# Adafruit_FXOS8700_FXAS21002_9_DoF_Breako.net
KiCad netlist of a schematic drawn in EAGLE
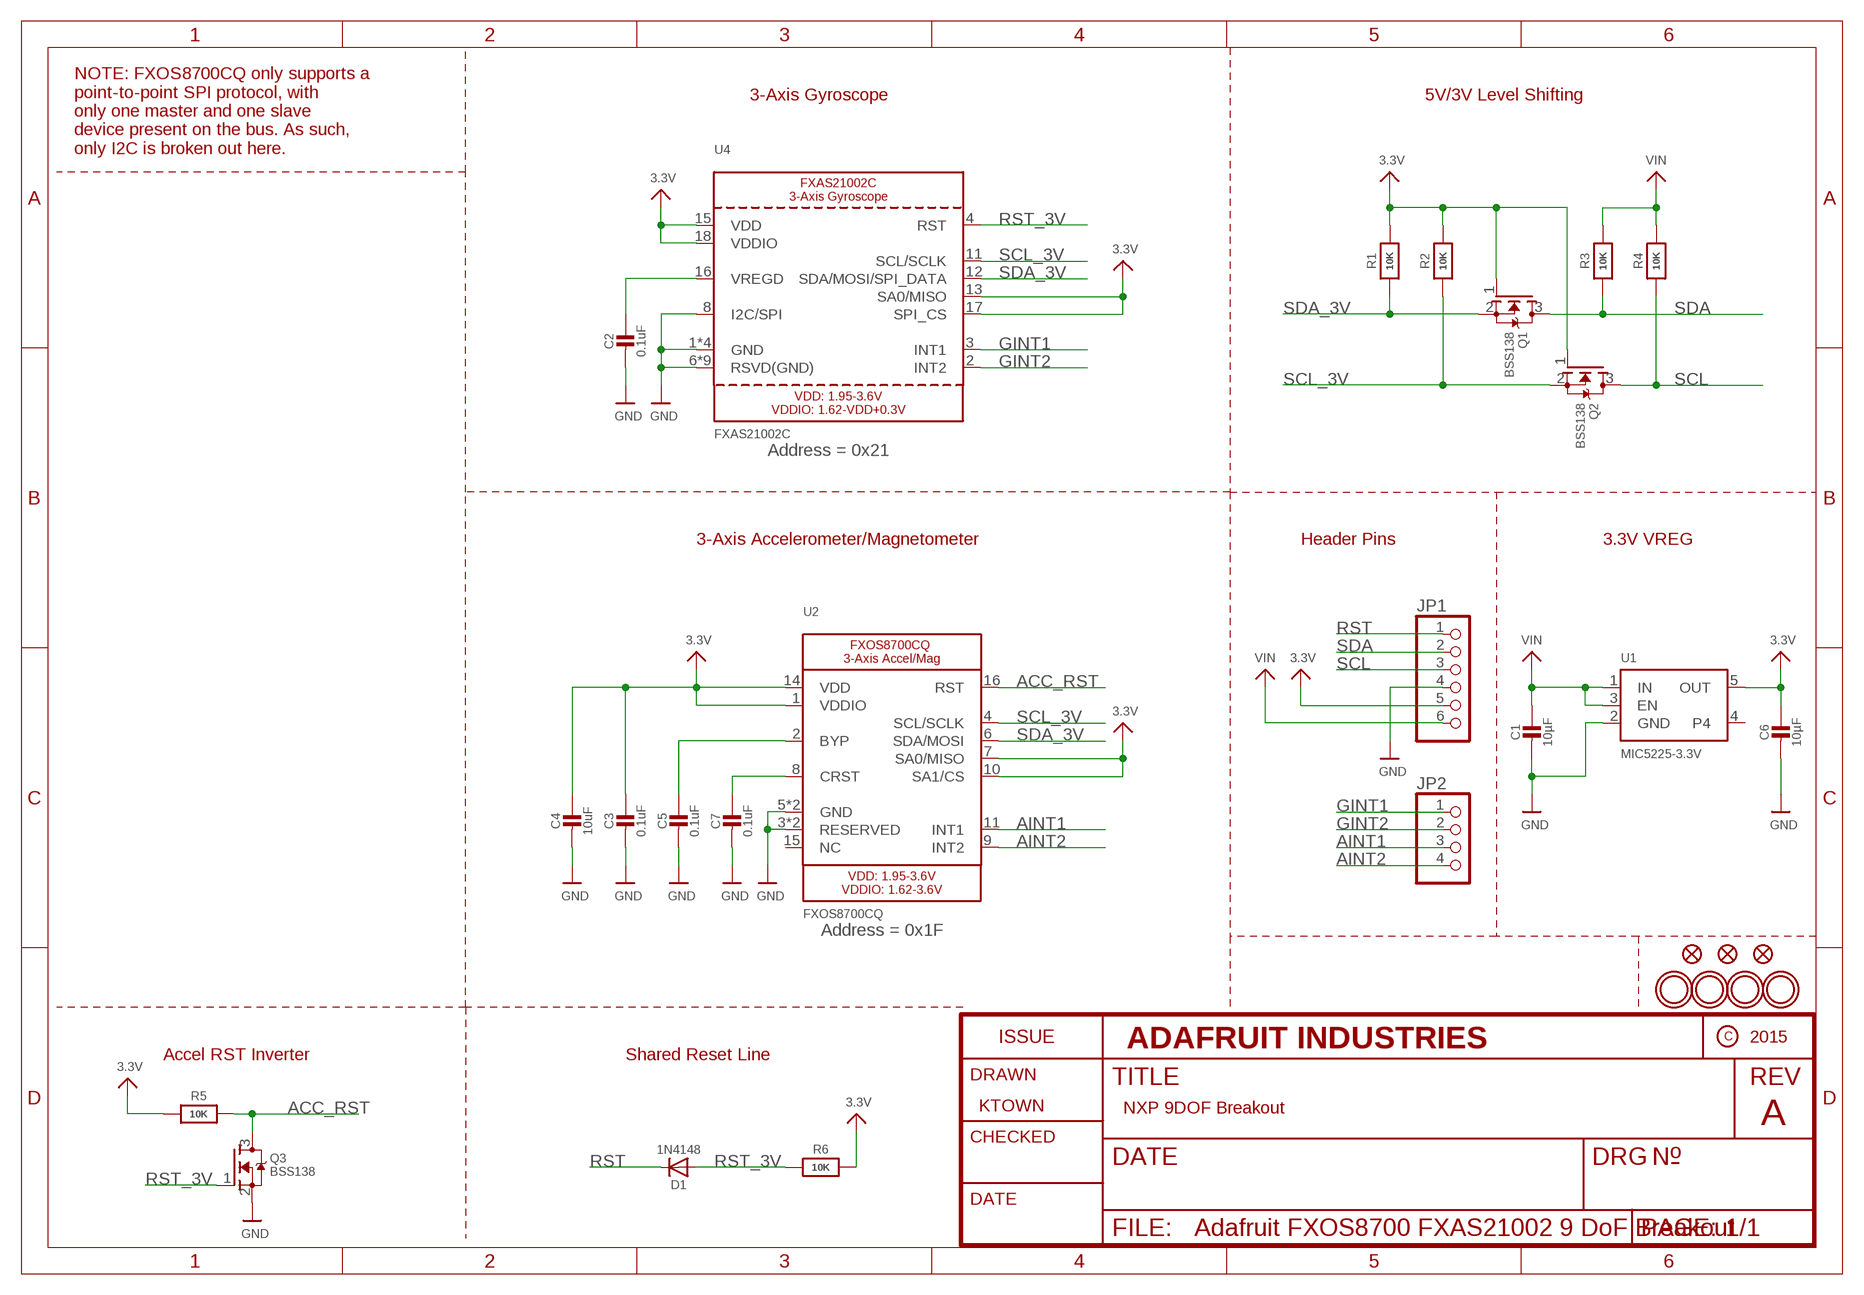
[diagram p0: schematic, sheet 1]

(export (version "E")
  (design (tool "Eeschema 10.0.6"))
  (components
    (comp (ref "C1")
      (value "10µF")
      (footprint "eagle-import:0805-NO")
      (libsource (lib "eagle-import") (part "CAP_CERAMIC0805-NOOUTLINE"))
    )
    (comp (ref "C2")
      (value "0.1uF")
      (footprint "eagle-import:0805-NO")
      (libsource (lib "eagle-import") (part "CAP_CERAMIC0805-NOOUTLINE"))
    )
    (comp (ref "C3")
      (value "0.1uF")
      (footprint "eagle-import:0805-NO")
      (libsource (lib "eagle-import") (part "CAP_CERAMIC0805-NOOUTLINE"))
    )
    (comp (ref "C4")
      (value "10uF")
      (footprint "eagle-import:0805-NO")
      (libsource (lib "eagle-import") (part "CAP_CERAMIC0805-NOOUTLINE"))
    )
    (comp (ref "C5")
      (value "0.1uF")
      (footprint "eagle-import:0805-NO")
      (libsource (lib "eagle-import") (part "CAP_CERAMIC0805-NOOUTLINE"))
    )
    (comp (ref "C6")
      (value "10µF")
      (footprint "eagle-import:0805-NO")
      (libsource (lib "eagle-import") (part "CAP_CERAMIC0805-NOOUTLINE"))
    )
    (comp (ref "C7")
      (value "0.1uF")
      (footprint "eagle-import:0805-NO")
      (libsource (lib "eagle-import") (part "CAP_CERAMIC0805-NOOUTLINE"))
    )
    (comp (ref "D1")
      (value "1N4148")
      (footprint "eagle-import:SOD-323")
      (libsource (lib "eagle-import") (part "DIODESOD-323"))
    )
    (comp (ref "FID1")
      (value "FIDUCIAL_1MM")
      (footprint "eagle-import:FIDUCIAL_1MM")
      (libsource (lib "eagle-import") (part "FIDUCIAL_1MM"))
    )
    (comp (ref "FID2")
      (value "FIDUCIAL_1MM")
      (footprint "eagle-import:FIDUCIAL_1MM")
      (libsource (lib "eagle-import") (part "FIDUCIAL_1MM"))
    )
    (comp (ref "FID3")
      (value "FIDUCIAL_1MM")
      (footprint "eagle-import:FIDUCIAL_1MM")
      (libsource (lib "eagle-import") (part "FIDUCIAL_1MM"))
    )
    (comp (ref "JP1")
      (value "HEADER-1X670MIL")
      (footprint "eagle-import:1X06_ROUND_70")
      (libsource (lib "eagle-import") (part "HEADER-1X670MIL"))
    )
    (comp (ref "JP2")
      (value "HEADER-1X4ROUND")
      (footprint "eagle-import:1X04_ROUND")
      (libsource (lib "eagle-import") (part "HEADER-1X4ROUND"))
    )
    (comp (ref "Q1")
      (value "BSS138")
      (footprint "eagle-import:SOT23-WIDE")
      (libsource (lib "eagle-import") (part "MOSFET-NWIDE"))
    )
    (comp (ref "Q2")
      (value "BSS138")
      (footprint "eagle-import:SOT23-WIDE")
      (libsource (lib "eagle-import") (part "MOSFET-NWIDE"))
    )
    (comp (ref "Q3")
      (value "BSS138")
      (footprint "eagle-import:SOT23-WIDE")
      (libsource (lib "eagle-import") (part "MOSFET-NWIDE"))
    )
    (comp (ref "R1")
      (value "10K")
      (footprint "eagle-import:0805-NO")
      (libsource (lib "eagle-import") (part "RESISTOR0805_NOOUTLINE"))
    )
    (comp (ref "R2")
      (value "10K")
      (footprint "eagle-import:0805-NO")
      (libsource (lib "eagle-import") (part "RESISTOR0805_NOOUTLINE"))
    )
    (comp (ref "R3")
      (value "10K")
      (footprint "eagle-import:0805-NO")
      (libsource (lib "eagle-import") (part "RESISTOR0805_NOOUTLINE"))
    )
    (comp (ref "R4")
      (value "10K")
      (footprint "eagle-import:0805-NO")
      (libsource (lib "eagle-import") (part "RESISTOR0805_NOOUTLINE"))
    )
    (comp (ref "R5")
      (value "10K")
      (footprint "eagle-import:0805-NO")
      (libsource (lib "eagle-import") (part "RESISTOR0805_NOOUTLINE"))
    )
    (comp (ref "R6")
      (value "10K")
      (footprint "eagle-import:0805-NO")
      (libsource (lib "eagle-import") (part "RESISTOR0805_NOOUTLINE"))
    )
    (comp (ref "U$1")
      (value "MOUNTINGHOLE2.5")
      (footprint "eagle-import:MOUNTINGHOLE_2.5_PLATED")
      (libsource (lib "eagle-import") (part "MOUNTINGHOLE2.5"))
    )
    (comp (ref "U$2")
      (value "MOUNTINGHOLE2.5")
      (footprint "eagle-import:MOUNTINGHOLE_2.5_PLATED")
      (libsource (lib "eagle-import") (part "MOUNTINGHOLE2.5"))
    )
    (comp (ref "U$3")
      (value "MOUNTINGHOLE2.5")
      (footprint "eagle-import:MOUNTINGHOLE_2.5_PLATED")
      (libsource (lib "eagle-import") (part "MOUNTINGHOLE2.5"))
    )
    (comp (ref "U$4")
      (value "MOUNTINGHOLE2.5")
      (footprint "eagle-import:MOUNTINGHOLE_2.5_PLATED")
      (libsource (lib "eagle-import") (part "MOUNTINGHOLE2.5"))
    )
    (comp (ref "U1")
      (value "MIC5225-3.3V")
      (footprint "eagle-import:SOT23-5")
      (libsource (lib "eagle-import") (part "VREG_SOT23-5"))
    )
    (comp (ref "U2")
      (value "FXOS8700CQ")
      (footprint "eagle-import:QFN16_3MM_FREESCALE_5X3")
      (libsource (lib "eagle-import") (part "ACCEL_MAG_FXOS8700CQ"))
    )
    (comp (ref "U4")
      (value "FXAS21002C")
      (footprint "eagle-import:QFN24_4MM_FREESCALE_7X5")
      (libsource (lib "eagle-import") (part "GYRO_FXAS21002C"))
    )
  )
  (nets
    (net (code "1") (name "/ACC_RST") (class "Default")
      (node (ref "Q3") (pin "3") (pinfunction "D_3") (pintype "bidirectional"))
      (node (ref "R5") (pin "2") (pinfunction "2_2") (pintype "passive"))
      (node (ref "U2") (pin "16") (pinfunction "RST_16") (pintype "bidirectional"))
    )
    (net (code "2") (name "/AINT1") (class "Default")
      (node (ref "JP2") (pin "3") (pinfunction "3_3") (pintype "passive"))
      (node (ref "U2") (pin "11") (pinfunction "INT1_11") (pintype "bidirectional"))
    )
    (net (code "3") (name "/AINT2") (class "Default")
      (node (ref "JP2") (pin "4") (pinfunction "4_4") (pintype "passive"))
      (node (ref "U2") (pin "9") (pinfunction "INT2_9") (pintype "bidirectional"))
    )
    (net (code "4") (name "/GINT1") (class "Default")
      (node (ref "JP2") (pin "1") (pinfunction "1_1") (pintype "passive"))
      (node (ref "U4") (pin "3") (pinfunction "INT1_3") (pintype "bidirectional"))
    )
    (net (code "5") (name "/GINT2") (class "Default")
      (node (ref "JP2") (pin "2") (pinfunction "2_2") (pintype "passive"))
      (node (ref "U4") (pin "2") (pinfunction "INT2_2") (pintype "bidirectional"))
    )
    (net (code "6") (name "/RST") (class "Default")
      (node (ref "D1") (pin "C") (pinfunction "C_C") (pintype "passive"))
      (node (ref "JP1") (pin "1") (pinfunction "1_1") (pintype "passive"))
    )
    (net (code "7") (name "/RST_3V") (class "Default")
      (node (ref "D1") (pin "A") (pinfunction "A_A") (pintype "passive"))
      (node (ref "Q3") (pin "1") (pinfunction "G_1") (pintype "bidirectional"))
      (node (ref "R6") (pin "1") (pinfunction "1_1") (pintype "passive"))
      (node (ref "U4") (pin "4") (pinfunction "RST_4") (pintype "bidirectional"))
    )
    (net (code "8") (name "/SCL") (class "Default")
      (node (ref "JP1") (pin "3") (pinfunction "3_3") (pintype "passive"))
      (node (ref "Q2") (pin "3") (pinfunction "D_3") (pintype "bidirectional"))
      (node (ref "R4") (pin "1") (pinfunction "1_1") (pintype "passive"))
    )
    (net (code "9") (name "/SCL_3V") (class "Default")
      (node (ref "Q2") (pin "2") (pinfunction "S_2") (pintype "bidirectional"))
      (node (ref "R2") (pin "1") (pinfunction "1_1") (pintype "passive"))
      (node (ref "U2") (pin "4") (pinfunction "SCL/SCLK_4") (pintype "bidirectional"))
      (node (ref "U4") (pin "11") (pinfunction "SCL/SCLK_11") (pintype "bidirectional"))
    )
    (net (code "10") (name "/SDA") (class "Default")
      (node (ref "JP1") (pin "2") (pinfunction "2_2") (pintype "passive"))
      (node (ref "Q1") (pin "3") (pinfunction "D_3") (pintype "bidirectional"))
      (node (ref "R3") (pin "1") (pinfunction "1_1") (pintype "passive"))
    )
    (net (code "11") (name "/SDA_3V") (class "Default")
      (node (ref "Q1") (pin "2") (pinfunction "S_2") (pintype "bidirectional"))
      (node (ref "R1") (pin "1") (pinfunction "1_1") (pintype "passive"))
      (node (ref "U2") (pin "6") (pinfunction "SDA/MOSI_6") (pintype "bidirectional"))
      (node (ref "U4") (pin "12") (pinfunction "SDA/MOSI/SPI_DATA_12") (pintype "bidirectional"))
    )
    (net (code "12") (name "3.3V") (class "Default")
      (node (ref "C3") (pin "1") (pinfunction "1_1") (pintype "passive"))
      (node (ref "C4") (pin "1") (pinfunction "1_1") (pintype "passive"))
      (node (ref "C6") (pin "1") (pinfunction "1_1") (pintype "passive"))
      (node (ref "JP1") (pin "5") (pinfunction "5_5") (pintype "passive"))
      (node (ref "Q1") (pin "1") (pinfunction "G_1") (pintype "bidirectional"))
      (node (ref "Q2") (pin "1") (pinfunction "G_1") (pintype "bidirectional"))
      (node (ref "R1") (pin "2") (pinfunction "2_2") (pintype "passive"))
      (node (ref "R2") (pin "2") (pinfunction "2_2") (pintype "passive"))
      (node (ref "R5") (pin "1") (pinfunction "1_1") (pintype "passive"))
      (node (ref "R6") (pin "2") (pinfunction "2_2") (pintype "passive"))
      (node (ref "U1") (pin "5") (pinfunction "OUT_5") (pintype "power_in"))
      (node (ref "U2") (pin "1") (pinfunction "VDDIO_1") (pintype "bidirectional"))
      (node (ref "U2") (pin "10") (pinfunction "SA1/CS_10") (pintype "bidirectional"))
      (node (ref "U2") (pin "14") (pinfunction "VDD_14") (pintype "bidirectional"))
      (node (ref "U2") (pin "7") (pinfunction "SA0/MISO_7") (pintype "bidirectional"))
      (node (ref "U4") (pin "13") (pinfunction "SA0/MISO_13") (pintype "bidirectional"))
      (node (ref "U4") (pin "15") (pinfunction "VDD_15") (pintype "bidirectional"))
      (node (ref "U4") (pin "17") (pinfunction "SPI_CS_17") (pintype "bidirectional"))
      (node (ref "U4") (pin "18") (pinfunction "VDDIO_18") (pintype "bidirectional"))
    )
    (net (code "13") (name "GND") (class "Default")
      (node (ref "C1") (pin "2") (pinfunction "2_2") (pintype "passive"))
      (node (ref "C2") (pin "2") (pinfunction "2_2") (pintype "passive"))
      (node (ref "C3") (pin "2") (pinfunction "2_2") (pintype "passive"))
      (node (ref "C4") (pin "2") (pinfunction "2_2") (pintype "passive"))
      (node (ref "C5") (pin "2") (pinfunction "2_2") (pintype "passive"))
      (node (ref "C6") (pin "2") (pinfunction "2_2") (pintype "passive"))
      (node (ref "C7") (pin "2") (pinfunction "2_2") (pintype "passive"))
      (node (ref "JP1") (pin "4") (pinfunction "4_4") (pintype "passive"))
      (node (ref "Q3") (pin "2") (pinfunction "S_2") (pintype "bidirectional"))
      (node (ref "U1") (pin "2") (pinfunction "GND_2") (pintype "power_in"))
      (node (ref "U2") (pin "12") (pinfunction "GND_12") (pintype "bidirectional"))
      (node (ref "U2") (pin "13") (pinfunction "RESERVED_13") (pintype "bidirectional"))
      (node (ref "U2") (pin "3") (pinfunction "RESERVED_3") (pintype "bidirectional"))
      (node (ref "U2") (pin "5") (pinfunction "GND_5") (pintype "bidirectional"))
      (node (ref "U4") (pin "1") (pinfunction "GND_1") (pintype "bidirectional"))
      (node (ref "U4") (pin "10") (pinfunction "RSVD(GND)_10") (pintype "bidirectional"))
      (node (ref "U4") (pin "14") (pinfunction "GND_14") (pintype "bidirectional"))
      (node (ref "U4") (pin "19") (pinfunction "GND_19") (pintype "bidirectional"))
      (node (ref "U4") (pin "20") (pinfunction "RSVD(GND)_20") (pintype "bidirectional"))
      (node (ref "U4") (pin "21") (pinfunction "RSVD(GND)_21") (pintype "bidirectional"))
      (node (ref "U4") (pin "22") (pinfunction "RSVD(GND)_22") (pintype "bidirectional"))
      (node (ref "U4") (pin "23") (pinfunction "RSVD(GND)_23") (pintype "bidirectional"))
      (node (ref "U4") (pin "24") (pinfunction "RSVD(GND)_24") (pintype "bidirectional"))
      (node (ref "U4") (pin "5") (pinfunction "GND_5") (pintype "bidirectional"))
      (node (ref "U4") (pin "6") (pinfunction "RSVD(GND)_6") (pintype "bidirectional"))
      (node (ref "U4") (pin "7") (pinfunction "RSVD(GND)_7") (pintype "bidirectional"))
      (node (ref "U4") (pin "8") (pinfunction "I2C/SPI_8") (pintype "bidirectional"))
      (node (ref "U4") (pin "9") (pinfunction "RSVD(GND)_9") (pintype "bidirectional"))
    )
    (net (code "14") (name "Net-(U2-BYP)") (class "Default")
      (node (ref "C5") (pin "1") (pinfunction "1_1") (pintype "passive"))
      (node (ref "U2") (pin "2") (pinfunction "BYP_2") (pintype "bidirectional"))
    )
    (net (code "15") (name "Net-(U2-CRST)") (class "Default")
      (node (ref "C7") (pin "1") (pinfunction "1_1") (pintype "passive"))
      (node (ref "U2") (pin "8") (pinfunction "CRST_8") (pintype "bidirectional"))
    )
    (net (code "16") (name "Net-(U4-VREGD)") (class "Default")
      (node (ref "C2") (pin "1") (pinfunction "1_1") (pintype "passive"))
      (node (ref "U4") (pin "16") (pinfunction "VREGD_16") (pintype "bidirectional"))
    )
    (net (code "17") (name "VIN") (class "Default")
      (node (ref "C1") (pin "1") (pinfunction "1_1") (pintype "passive"))
      (node (ref "JP1") (pin "6") (pinfunction "6_6") (pintype "passive"))
      (node (ref "R3") (pin "2") (pinfunction "2_2") (pintype "passive"))
      (node (ref "R4") (pin "2") (pinfunction "2_2") (pintype "passive"))
      (node (ref "U1") (pin "1") (pinfunction "IN_1") (pintype "power_in"))
      (node (ref "U1") (pin "3") (pinfunction "EN_3") (pintype "input"))
    )
    (net (code "18") (name "unconnected-(U1-P4-Pad4)") (class "Default")
      (node (ref "U1") (pin "4") (pinfunction "P4_4") (pintype "bidirectional"))
    )
    (net (code "19") (name "unconnected-(U2-NC-Pad15)") (class "Default")
      (node (ref "U2") (pin "15") (pinfunction "NC_15") (pintype "bidirectional"))
    )
  )
)
